# Blip_V1_5.net
KiCad netlist of a schematic drawn in EAGLE
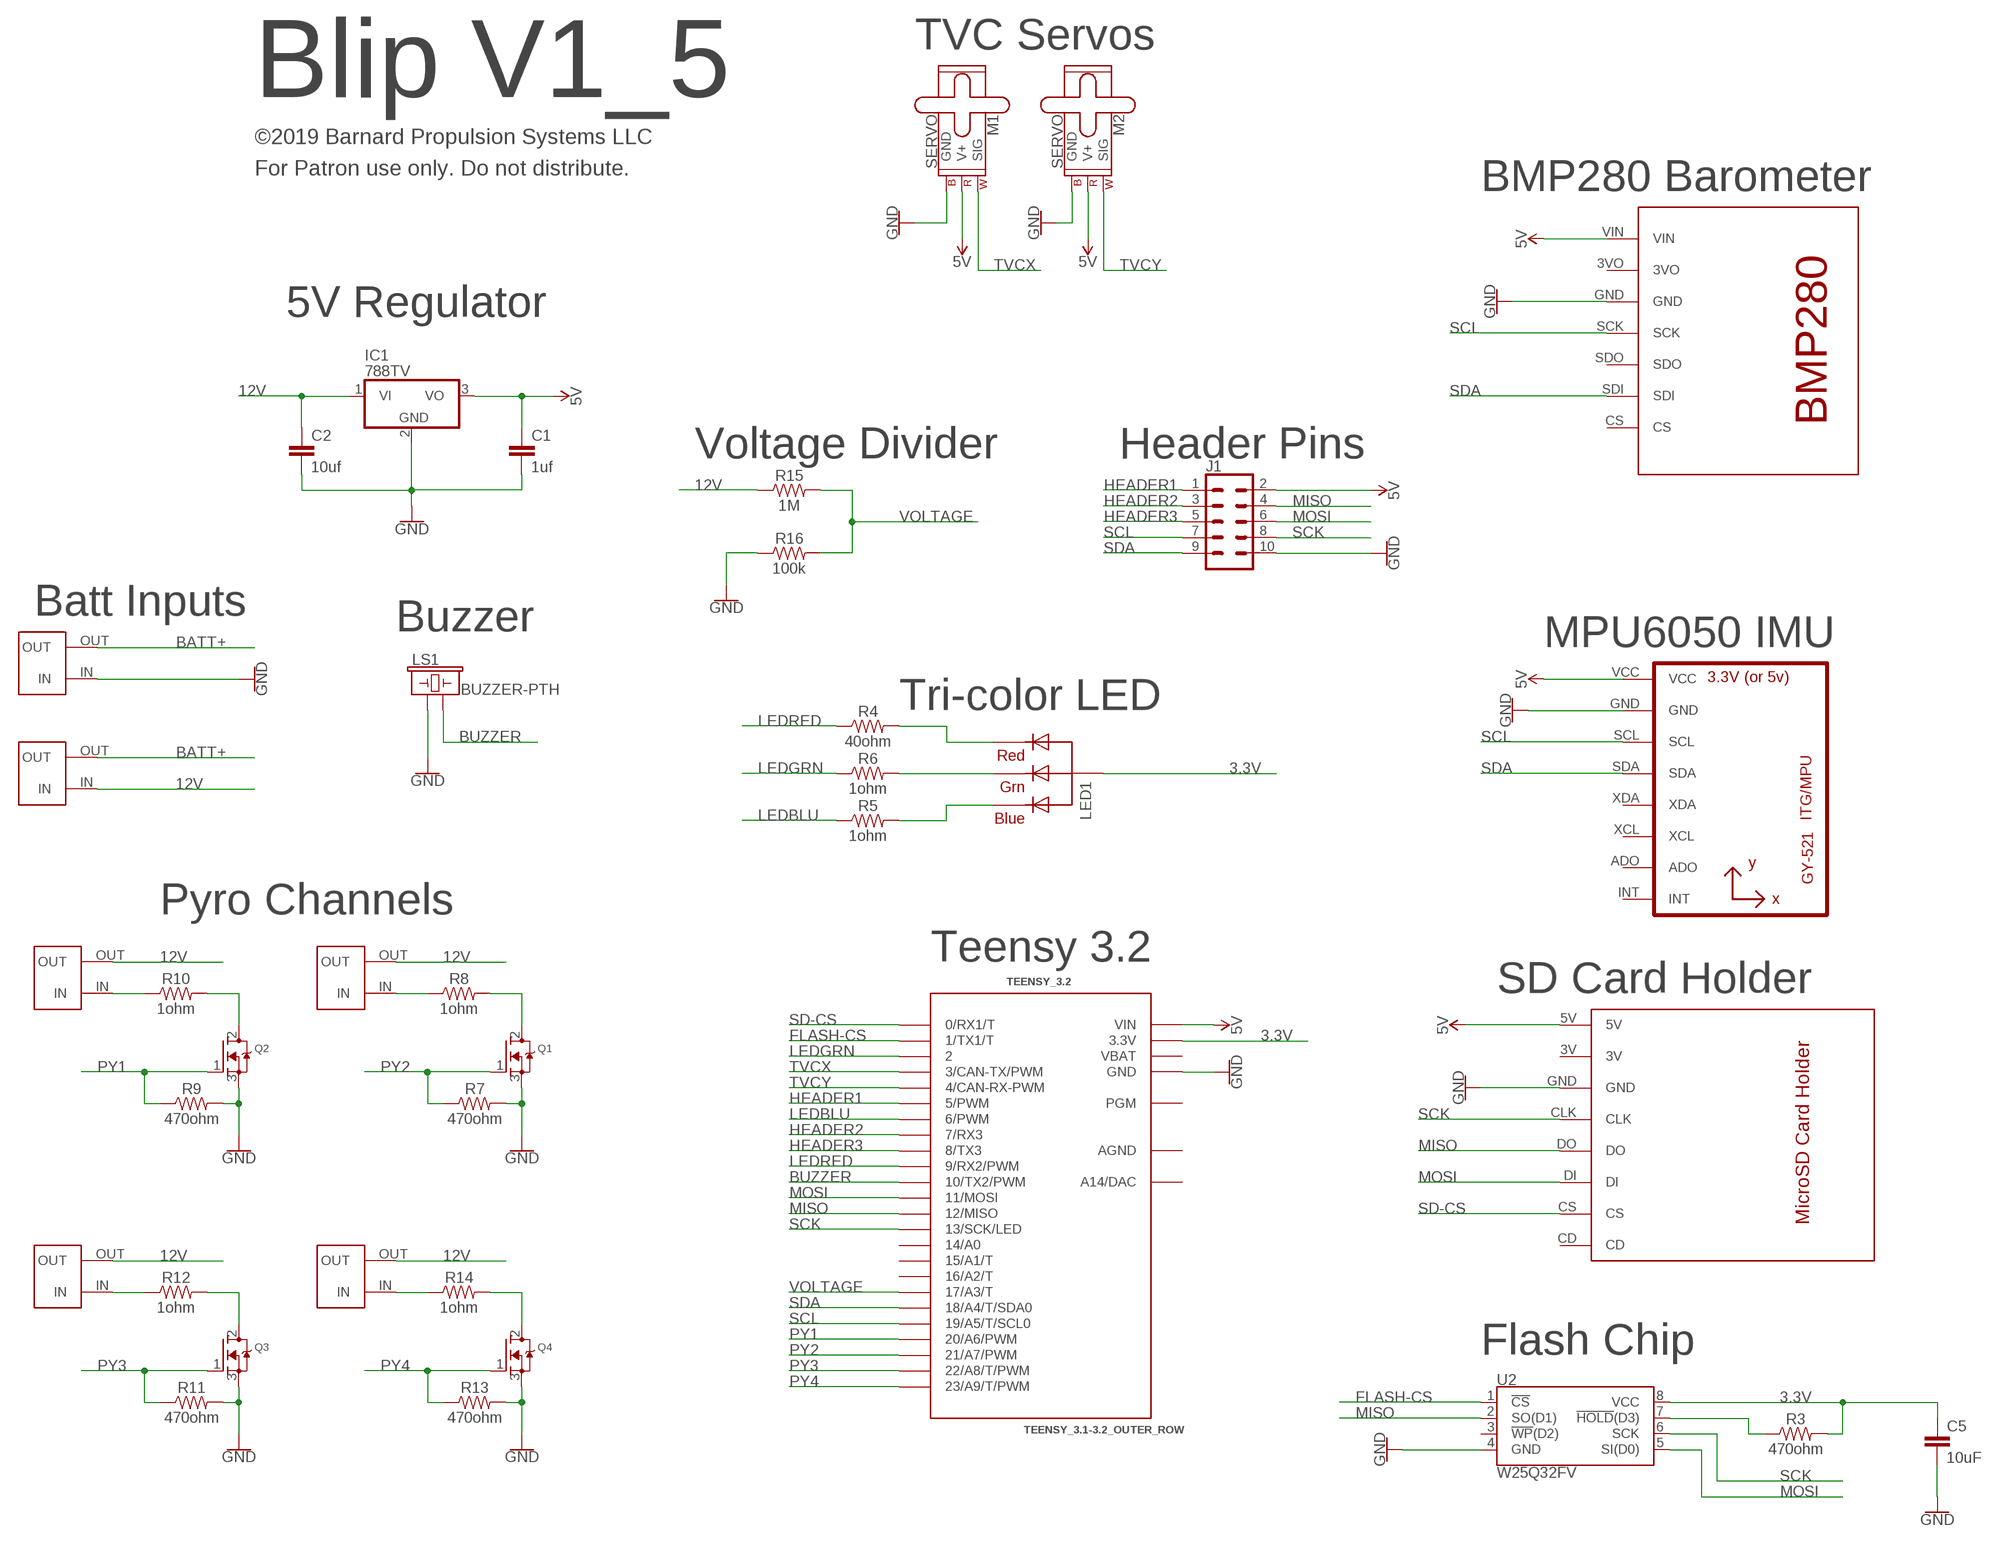
[diagram p0: schematic, sheet 1]

(export (version "E")
  (design (tool "Eeschema 10.0.6"))
  (components
    (comp (ref "C1")
      (value "1uf")
      (footprint "eagle-import:CAP-PTH-2.54")
      (libsource (lib "eagle-import") (part "22PF-PTH-2.54MM-200V-5%"))
    )
    (comp (ref "C2")
      (value "10uf")
      (footprint "eagle-import:CAP-PTH-2.54")
      (libsource (lib "eagle-import") (part "22PF-PTH-2.54MM-200V-5%"))
    )
    (comp (ref "C5")
      (value "10uF")
      (footprint "eagle-import:CAP-PTH-2.54")
      (libsource (lib "eagle-import") (part "22PF-PTH-2.54MM-200V-5%"))
    )
    (comp (ref "IC1")
      (value "788TV")
      (footprint "eagle-import:TO220V")
      (libsource (lib "eagle-import") (part "78TV8"))
    )
    (comp (ref "J1")
      (value "CONN_05X2NO_SILK")
      (footprint "eagle-import:2X5_NOSILK")
      (libsource (lib "eagle-import") (part "CONN_05X2NO_SILK"))
    )
    (comp (ref "LED1")
      (value "RGBLED_CA-5MM")
      (footprint "eagle-import:LED5MMRGB")
      (libsource (lib "eagle-import") (part "RGBLED_CA-5MM"))
    )
    (comp (ref "LS1")
      (value "BUZZER-PTH")
      (footprint "eagle-import:BUZZER-12MM")
      (libsource (lib "eagle-import") (part "BUZZER-PTH"))
    )
    (comp (ref "M1")
      (value "SERVO")
      (footprint "eagle-import:1X03")
      (libsource (lib "eagle-import") (part "SERVO"))
    )
    (comp (ref "M2")
      (value "SERVO")
      (footprint "eagle-import:1X03")
      (libsource (lib "eagle-import") (part "SERVO"))
    )
    (comp (ref "Q1")
      (value "MOSFET-NGDS_TO220V")
      (footprint "eagle-import:TO220V")
      (libsource (lib "eagle-import") (part "MOSFET-NGDS_TO220V"))
    )
    (comp (ref "Q2")
      (value "MOSFET-NGDS_TO220V")
      (footprint "eagle-import:TO220V")
      (libsource (lib "eagle-import") (part "MOSFET-NGDS_TO220V"))
    )
    (comp (ref "Q3")
      (value "MOSFET-NGDS_TO220V")
      (footprint "eagle-import:TO220V")
      (libsource (lib "eagle-import") (part "MOSFET-NGDS_TO220V"))
    )
    (comp (ref "Q4")
      (value "MOSFET-NGDS_TO220V")
      (footprint "eagle-import:TO220V")
      (libsource (lib "eagle-import") (part "MOSFET-NGDS_TO220V"))
    )
    (comp (ref "R3")
      (value "470ohm")
      (footprint "eagle-import:AXIAL-0.3")
      (libsource (lib "eagle-import") (part "10MOHM-HORIZ-1/4W-5%"))
    )
    (comp (ref "R4")
      (value "40ohm")
      (footprint "eagle-import:AXIAL-0.3")
      (libsource (lib "eagle-import") (part "10MOHM-HORIZ-1/4W-5%"))
    )
    (comp (ref "R5")
      (value "1ohm")
      (footprint "eagle-import:AXIAL-0.3")
      (libsource (lib "eagle-import") (part "10MOHM-HORIZ-1/4W-5%"))
    )
    (comp (ref "R6")
      (value "1ohm")
      (footprint "eagle-import:AXIAL-0.3")
      (libsource (lib "eagle-import") (part "10MOHM-HORIZ-1/4W-5%"))
    )
    (comp (ref "R7")
      (value "470ohm")
      (footprint "eagle-import:AXIAL-0.3")
      (libsource (lib "eagle-import") (part "10MOHM-HORIZ-1/4W-5%"))
    )
    (comp (ref "R8")
      (value "1ohm")
      (footprint "eagle-import:AXIAL-0.3")
      (libsource (lib "eagle-import") (part "10MOHM-HORIZ-1/4W-5%"))
    )
    (comp (ref "R9")
      (value "470ohm")
      (footprint "eagle-import:AXIAL-0.3")
      (libsource (lib "eagle-import") (part "10MOHM-HORIZ-1/4W-5%"))
    )
    (comp (ref "R10")
      (value "1ohm")
      (footprint "eagle-import:AXIAL-0.3")
      (libsource (lib "eagle-import") (part "10MOHM-HORIZ-1/4W-5%"))
    )
    (comp (ref "R11")
      (value "470ohm")
      (footprint "eagle-import:AXIAL-0.3")
      (libsource (lib "eagle-import") (part "10MOHM-HORIZ-1/4W-5%"))
    )
    (comp (ref "R12")
      (value "1ohm")
      (footprint "eagle-import:AXIAL-0.3")
      (libsource (lib "eagle-import") (part "10MOHM-HORIZ-1/4W-5%"))
    )
    (comp (ref "R13")
      (value "470ohm")
      (footprint "eagle-import:AXIAL-0.3")
      (libsource (lib "eagle-import") (part "10MOHM-HORIZ-1/4W-5%"))
    )
    (comp (ref "R14")
      (value "1ohm")
      (footprint "eagle-import:AXIAL-0.3")
      (libsource (lib "eagle-import") (part "10MOHM-HORIZ-1/4W-5%"))
    )
    (comp (ref "R15")
      (value "1M")
      (footprint "eagle-import:AXIAL-0.3")
      (libsource (lib "eagle-import") (part "10MOHM-HORIZ-1/4W-5%"))
    )
    (comp (ref "R16")
      (value "100k")
      (footprint "eagle-import:AXIAL-0.3")
      (libsource (lib "eagle-import") (part "10MOHM-HORIZ-1/4W-5%"))
    )
    (comp (ref "TEENSY_3.2")
      (value "TEENSY_3.1-3.2_OUTER_ROW")
      (footprint "eagle-import:TEENSY_3.0-3.2&LC_OUTER_ROW")
      (libsource (lib "eagle-import") (part "TEENSY_3.1-3.2_OUTER_ROW"))
    )
    (comp (ref "U$2")
      (value "BMP280")
      (footprint "eagle-import:BMP280")
      (libsource (lib "eagle-import") (part "BMP280"))
    )
    (comp (ref "U$3")
      (value "MICROSDCARDHOLDER")
      (footprint "eagle-import:SDCARDHOLDER")
      (libsource (lib "eagle-import") (part "MICROSDCARDHOLDER"))
    )
    (comp (ref "U$4")
      (value "BLACKTERMBLOCK")
      (footprint "eagle-import:BLACKTERMBLOCK")
      (libsource (lib "eagle-import") (part "BLACKTERMBLOCK"))
    )
    (comp (ref "U$5")
      (value "BLACKTERMBLOCK")
      (footprint "eagle-import:BLACKTERMBLOCK")
      (libsource (lib "eagle-import") (part "BLACKTERMBLOCK"))
    )
    (comp (ref "U$6")
      (value "BLACKTERMBLOCK")
      (footprint "eagle-import:BLACKTERMBLOCK")
      (libsource (lib "eagle-import") (part "BLACKTERMBLOCK"))
    )
    (comp (ref "U$7")
      (value "BLACKTERMBLOCK")
      (footprint "eagle-import:BLACKTERMBLOCK")
      (libsource (lib "eagle-import") (part "BLACKTERMBLOCK"))
    )
    (comp (ref "U$8")
      (value "BLACKTERMBLOCK")
      (footprint "eagle-import:BLACKTERMBLOCK")
      (libsource (lib "eagle-import") (part "BLACKTERMBLOCK"))
    )
    (comp (ref "U$9")
      (value "BLACKTERMBLOCK")
      (footprint "eagle-import:BLACKTERMBLOCK")
      (libsource (lib "eagle-import") (part "BLACKTERMBLOCK"))
    )
    (comp (ref "U1")
      (value "GY-521MPU6050")
      (footprint "eagle-import:GY-521")
      (libsource (lib "eagle-import") (part "GY-521MPU6050"))
    )
    (comp (ref "U2")
      (value "W25Q32FV")
      (footprint "eagle-import:SOIC-8")
      (libsource (lib "eagle-import") (part "W25Q32FVSS"))
    )
  )
  (nets
    (net (code "1") (name "/3.3V") (class "Default")
      (node (ref "C5") (pin "1") (pinfunction "1_1") (pintype "passive"))
      (node (ref "LED1") (pin "2") (pinfunction "VCC_2") (pintype "bidirectional"))
      (node (ref "R3") (pin "P$2") (pinfunction "2_P$2") (pintype "passive"))
      (node (ref "TEENSY_3.2") (pin "3.3V") (pinfunction "3.3V_3.3V") (pintype "power_in"))
      (node (ref "TEENSY_3.2") (pin "3.3V1") (pinfunction "3.3V_3.3V1") (pintype "power_in"))
      (node (ref "U2") (pin "8") (pinfunction "VCC_8") (pintype "bidirectional"))
    )
    (net (code "2") (name "/12V") (class "Default")
      (node (ref "C2") (pin "1") (pinfunction "1_1") (pintype "passive"))
      (node (ref "IC1") (pin "1") (pinfunction "VI_1") (pintype "input"))
      (node (ref "R15") (pin "P$1") (pinfunction "1_P$1") (pintype "passive"))
      (node (ref "U$4") (pin "OUT") (pinfunction "OUT_OUT") (pintype "bidirectional"))
      (node (ref "U$5") (pin "OUT") (pinfunction "OUT_OUT") (pintype "bidirectional"))
      (node (ref "U$6") (pin "OUT") (pinfunction "OUT_OUT") (pintype "bidirectional"))
      (node (ref "U$7") (pin "OUT") (pinfunction "OUT_OUT") (pintype "bidirectional"))
      (node (ref "U$9") (pin "IN") (pinfunction "IN_IN") (pintype "bidirectional"))
    )
    (net (code "3") (name "/AGND") (class "Default")
      (node (ref "TEENSY_3.2") (pin "AGND") (pinfunction "AGND_AGND") (pintype "power_in"))
    )
    (net (code "4") (name "/BATT+") (class "Default")
      (node (ref "U$8") (pin "OUT") (pinfunction "OUT_OUT") (pintype "bidirectional"))
      (node (ref "U$9") (pin "OUT") (pinfunction "OUT_OUT") (pintype "bidirectional"))
    )
    (net (code "5") (name "/BUZZER") (class "Default")
      (node (ref "LS1") (pin "-") (pinfunction "2_-") (pintype "passive"))
      (node (ref "TEENSY_3.2") (pin "10") (pinfunction "10/TX2/PWM_10") (pintype "bidirectional"))
    )
    (net (code "6") (name "/FLASH-CS") (class "Default")
      (node (ref "TEENSY_3.2") (pin "1") (pinfunction "1/TX1/T_1") (pintype "bidirectional"))
      (node (ref "U2") (pin "1") (pinfunction "~{CS}_1") (pintype "bidirectional"))
    )
    (net (code "7") (name "/HEADER1") (class "Default")
      (node (ref "J1") (pin "1") (pinfunction "1_1") (pintype "passive"))
      (node (ref "TEENSY_3.2") (pin "5") (pinfunction "5/PWM_5") (pintype "bidirectional"))
    )
    (net (code "8") (name "/HEADER2") (class "Default")
      (node (ref "J1") (pin "3") (pinfunction "3_3") (pintype "passive"))
      (node (ref "TEENSY_3.2") (pin "7") (pinfunction "7/RX3_7") (pintype "bidirectional"))
    )
    (net (code "9") (name "/HEADER3") (class "Default")
      (node (ref "J1") (pin "5") (pinfunction "5_5") (pintype "passive"))
      (node (ref "TEENSY_3.2") (pin "8") (pinfunction "8/TX3_8") (pintype "bidirectional"))
    )
    (net (code "10") (name "/LEDBLU") (class "Default")
      (node (ref "R5") (pin "P$1") (pinfunction "1_P$1") (pintype "passive"))
      (node (ref "TEENSY_3.2") (pin "6") (pinfunction "6/PWM_6") (pintype "bidirectional"))
    )
    (net (code "11") (name "/LEDGRN") (class "Default")
      (node (ref "R6") (pin "P$1") (pinfunction "1_P$1") (pintype "passive"))
      (node (ref "TEENSY_3.2") (pin "2") (pinfunction "2_2") (pintype "bidirectional"))
    )
    (net (code "12") (name "/LEDRED") (class "Default")
      (node (ref "R4") (pin "P$1") (pinfunction "1_P$1") (pintype "passive"))
      (node (ref "TEENSY_3.2") (pin "9") (pinfunction "9/RX2/PWM_9") (pintype "bidirectional"))
    )
    (net (code "13") (name "/MISO") (class "Default")
      (node (ref "J1") (pin "4") (pinfunction "4_4") (pintype "passive"))
      (node (ref "TEENSY_3.2") (pin "12") (pinfunction "12/MISO_12") (pintype "bidirectional"))
      (node (ref "U$3") (pin "DO") (pinfunction "DO_DO") (pintype "bidirectional"))
      (node (ref "U2") (pin "2") (pinfunction "SO(D1)_2") (pintype "bidirectional"))
    )
    (net (code "14") (name "/MOSI") (class "Default")
      (node (ref "J1") (pin "6") (pinfunction "6_6") (pintype "passive"))
      (node (ref "TEENSY_3.2") (pin "11") (pinfunction "11/MOSI_11") (pintype "bidirectional"))
      (node (ref "U$3") (pin "DI") (pinfunction "DI_DI") (pintype "bidirectional"))
      (node (ref "U2") (pin "5") (pinfunction "SI(D0)_5") (pintype "bidirectional"))
    )
    (net (code "15") (name "/PY1") (class "Default")
      (node (ref "Q2") (pin "1") (pinfunction "G_1") (pintype "bidirectional"))
      (node (ref "R9") (pin "P$1") (pinfunction "1_P$1") (pintype "passive"))
      (node (ref "TEENSY_3.2") (pin "20/A6") (pinfunction "20/A6/PWM_20/A6") (pintype "bidirectional"))
    )
    (net (code "16") (name "/PY2") (class "Default")
      (node (ref "Q1") (pin "1") (pinfunction "G_1") (pintype "bidirectional"))
      (node (ref "R7") (pin "P$1") (pinfunction "1_P$1") (pintype "passive"))
      (node (ref "TEENSY_3.2") (pin "21/A7") (pinfunction "21/A7/PWM_21/A7") (pintype "bidirectional"))
    )
    (net (code "17") (name "/PY3") (class "Default")
      (node (ref "Q3") (pin "1") (pinfunction "G_1") (pintype "bidirectional"))
      (node (ref "R11") (pin "P$1") (pinfunction "1_P$1") (pintype "passive"))
      (node (ref "TEENSY_3.2") (pin "22/A8") (pinfunction "22/A8/T/PWM_22/A8") (pintype "bidirectional"))
    )
    (net (code "18") (name "/PY4") (class "Default")
      (node (ref "Q4") (pin "1") (pinfunction "G_1") (pintype "bidirectional"))
      (node (ref "R13") (pin "P$1") (pinfunction "1_P$1") (pintype "passive"))
      (node (ref "TEENSY_3.2") (pin "23/A9") (pinfunction "23/A9/T/PWM_23/A9") (pintype "bidirectional"))
    )
    (net (code "19") (name "/SCK") (class "Default")
      (node (ref "J1") (pin "8") (pinfunction "8_8") (pintype "passive"))
      (node (ref "TEENSY_3.2") (pin "13") (pinfunction "13/SCK/LED_13") (pintype "bidirectional"))
      (node (ref "U$3") (pin "CLK") (pinfunction "CLK_CLK") (pintype "bidirectional"))
      (node (ref "U2") (pin "6") (pinfunction "SCK_6") (pintype "bidirectional"))
    )
    (net (code "20") (name "/SCL") (class "Default")
      (node (ref "J1") (pin "7") (pinfunction "7_7") (pintype "passive"))
      (node (ref "TEENSY_3.2") (pin "19/A5") (pinfunction "19/A5/T/SCL0_19/A5") (pintype "bidirectional"))
      (node (ref "U$2") (pin "SCK") (pinfunction "SCK_SCK") (pintype "bidirectional"))
      (node (ref "U1") (pin "SCL") (pinfunction "SCL_SCL") (pintype "bidirectional"))
    )
    (net (code "21") (name "/SD-CS") (class "Default")
      (node (ref "TEENSY_3.2") (pin "0") (pinfunction "0/RX1/T_0") (pintype "bidirectional"))
      (node (ref "U$3") (pin "CS") (pinfunction "CS_CS") (pintype "bidirectional"))
    )
    (net (code "22") (name "/SDA") (class "Default")
      (node (ref "J1") (pin "9") (pinfunction "9_9") (pintype "passive"))
      (node (ref "TEENSY_3.2") (pin "18/A4") (pinfunction "18/A4/T/SDA0_18/A4") (pintype "bidirectional"))
      (node (ref "U$2") (pin "SDI") (pinfunction "SDI_SDI") (pintype "bidirectional"))
      (node (ref "U1") (pin "SDA") (pinfunction "SDA_SDA") (pintype "bidirectional"))
    )
    (net (code "23") (name "/TVCX") (class "Default")
      (node (ref "M1") (pin "1") (pinfunction "SIG_1") (pintype "bidirectional"))
      (node (ref "TEENSY_3.2") (pin "3") (pinfunction "3/CAN-TX/PWM_3") (pintype "bidirectional"))
    )
    (net (code "24") (name "/TVCY") (class "Default")
      (node (ref "M2") (pin "1") (pinfunction "SIG_1") (pintype "bidirectional"))
      (node (ref "TEENSY_3.2") (pin "4") (pinfunction "4/CAN-RX-PWM_4") (pintype "bidirectional"))
    )
    (net (code "25") (name "/VBAT") (class "Default")
      (node (ref "TEENSY_3.2") (pin "VBAT") (pinfunction "VBAT_VBAT") (pintype "power_in"))
    )
    (net (code "26") (name "/VOLTAGE") (class "Default")
      (node (ref "R15") (pin "P$2") (pinfunction "2_P$2") (pintype "passive"))
      (node (ref "R16") (pin "P$2") (pinfunction "2_P$2") (pintype "passive"))
      (node (ref "TEENSY_3.2") (pin "17/A3") (pinfunction "17/A3/T_17/A3") (pintype "bidirectional"))
    )
    (net (code "27") (name "5V") (class "Default")
      (node (ref "C1") (pin "1") (pinfunction "1_1") (pintype "passive"))
      (node (ref "IC1") (pin "3") (pinfunction "VO_3") (pintype "passive"))
      (node (ref "J1") (pin "2") (pinfunction "2_2") (pintype "passive"))
      (node (ref "M1") (pin "2") (pinfunction "V+_2") (pintype "bidirectional"))
      (node (ref "M2") (pin "2") (pinfunction "V+_2") (pintype "bidirectional"))
      (node (ref "TEENSY_3.2") (pin "VIN") (pinfunction "VIN_VIN") (pintype "power_in"))
      (node (ref "U$2") (pin "VIN") (pinfunction "VIN_VIN") (pintype "bidirectional"))
      (node (ref "U$3") (pin "5V") (pinfunction "5V_5V") (pintype "bidirectional"))
      (node (ref "U1") (pin "VCC") (pinfunction "VCC_VCC") (pintype "bidirectional"))
    )
    (net (code "28") (name "GND") (class "Default")
      (node (ref "C1") (pin "2") (pinfunction "2_2") (pintype "passive"))
      (node (ref "C2") (pin "2") (pinfunction "2_2") (pintype "passive"))
      (node (ref "C5") (pin "2") (pinfunction "2_2") (pintype "passive"))
      (node (ref "IC1") (pin "2") (pinfunction "GND_2") (pintype "passive"))
      (node (ref "J1") (pin "10") (pinfunction "10_10") (pintype "passive"))
      (node (ref "LS1") (pin "+") (pinfunction "1_+") (pintype "passive"))
      (node (ref "M1") (pin "3") (pinfunction "GND_3") (pintype "bidirectional"))
      (node (ref "M2") (pin "3") (pinfunction "GND_3") (pintype "bidirectional"))
      (node (ref "Q1") (pin "3") (pinfunction "S_3") (pintype "bidirectional"))
      (node (ref "Q2") (pin "3") (pinfunction "S_3") (pintype "bidirectional"))
      (node (ref "Q3") (pin "3") (pinfunction "S_3") (pintype "bidirectional"))
      (node (ref "Q4") (pin "3") (pinfunction "S_3") (pintype "bidirectional"))
      (node (ref "R11") (pin "P$2") (pinfunction "2_P$2") (pintype "passive"))
      (node (ref "R13") (pin "P$2") (pinfunction "2_P$2") (pintype "passive"))
      (node (ref "R16") (pin "P$1") (pinfunction "1_P$1") (pintype "passive"))
      (node (ref "R7") (pin "P$2") (pinfunction "2_P$2") (pintype "passive"))
      (node (ref "R9") (pin "P$2") (pinfunction "2_P$2") (pintype "passive"))
      (node (ref "TEENSY_3.2") (pin "GND") (pinfunction "GND_GND") (pintype "power_in"))
      (node (ref "TEENSY_3.2") (pin "GND1") (pinfunction "GND_GND1") (pintype "power_in"))
      (node (ref "U$2") (pin "GND") (pinfunction "GND_GND") (pintype "bidirectional"))
      (node (ref "U$3") (pin "GND") (pinfunction "GND_GND") (pintype "bidirectional"))
      (node (ref "U$8") (pin "IN") (pinfunction "IN_IN") (pintype "bidirectional"))
      (node (ref "U1") (pin "GND") (pinfunction "GND_GND") (pintype "bidirectional"))
      (node (ref "U2") (pin "4") (pinfunction "GND_4") (pintype "bidirectional"))
    )
    (net (code "29") (name "Net-(LED1-BLUE)") (class "Default")
      (node (ref "LED1") (pin "4") (pinfunction "BLUE_4") (pintype "bidirectional"))
      (node (ref "R5") (pin "P$2") (pinfunction "2_P$2") (pintype "passive"))
    )
    (net (code "30") (name "Net-(LED1-GREEN)") (class "Default")
      (node (ref "LED1") (pin "3") (pinfunction "GREEN_3") (pintype "bidirectional"))
      (node (ref "R6") (pin "P$2") (pinfunction "2_P$2") (pintype "passive"))
    )
    (net (code "31") (name "Net-(LED1-RED)") (class "Default")
      (node (ref "LED1") (pin "1") (pinfunction "RED_1") (pintype "bidirectional"))
      (node (ref "R4") (pin "P$2") (pinfunction "2_P$2") (pintype "passive"))
    )
    (net (code "32") (name "Net-(Q1-D)") (class "Default")
      (node (ref "Q1") (pin "2") (pinfunction "D_2") (pintype "bidirectional"))
      (node (ref "R8") (pin "P$2") (pinfunction "2_P$2") (pintype "passive"))
    )
    (net (code "33") (name "Net-(Q2-D)") (class "Default")
      (node (ref "Q2") (pin "2") (pinfunction "D_2") (pintype "bidirectional"))
      (node (ref "R10") (pin "P$2") (pinfunction "2_P$2") (pintype "passive"))
    )
    (net (code "34") (name "Net-(Q3-D)") (class "Default")
      (node (ref "Q3") (pin "2") (pinfunction "D_2") (pintype "bidirectional"))
      (node (ref "R12") (pin "P$2") (pinfunction "2_P$2") (pintype "passive"))
    )
    (net (code "35") (name "Net-(Q4-D)") (class "Default")
      (node (ref "Q4") (pin "2") (pinfunction "D_2") (pintype "bidirectional"))
      (node (ref "R14") (pin "P$2") (pinfunction "2_P$2") (pintype "passive"))
    )
    (net (code "36") (name "Net-(R3-1)") (class "Default")
      (node (ref "R3") (pin "P$1") (pinfunction "1_P$1") (pintype "passive"))
      (node (ref "U2") (pin "7") (pinfunction "~{HOLD}(D3)_7") (pintype "bidirectional"))
    )
    (net (code "37") (name "Net-(R8-1)") (class "Default")
      (node (ref "R8") (pin "P$1") (pinfunction "1_P$1") (pintype "passive"))
      (node (ref "U$4") (pin "IN") (pinfunction "IN_IN") (pintype "bidirectional"))
    )
    (net (code "38") (name "Net-(R10-1)") (class "Default")
      (node (ref "R10") (pin "P$1") (pinfunction "1_P$1") (pintype "passive"))
      (node (ref "U$5") (pin "IN") (pinfunction "IN_IN") (pintype "bidirectional"))
    )
    (net (code "39") (name "Net-(R12-1)") (class "Default")
      (node (ref "R12") (pin "P$1") (pinfunction "1_P$1") (pintype "passive"))
      (node (ref "U$6") (pin "IN") (pinfunction "IN_IN") (pintype "bidirectional"))
    )
    (net (code "40") (name "Net-(R14-1)") (class "Default")
      (node (ref "R14") (pin "P$1") (pinfunction "1_P$1") (pintype "passive"))
      (node (ref "U$7") (pin "IN") (pinfunction "IN_IN") (pintype "bidirectional"))
    )
    (net (code "41") (name "unconnected-(TEENSY_3.2-15{slash}A1{slash}T-Pad15{slash}A1)") (class "Default")
      (node (ref "TEENSY_3.2") (pin "15/A1") (pinfunction "15/A1/T_15/A1") (pintype "bidirectional"))
    )
    (net (code "42") (name "unconnected-(TEENSY_3.2-16{slash}A2{slash}T-Pad16{slash}A2)") (class "Default")
      (node (ref "TEENSY_3.2") (pin "16/A2") (pinfunction "16/A2/T_16/A2") (pintype "bidirectional"))
    )
    (net (code "43") (name "unconnected-(TEENSY_3.2-A14{slash}DAC-PadRESET{slash}DAC)") (class "Default")
      (node (ref "TEENSY_3.2") (pin "RESET/DAC") (pinfunction "A14/DAC_RESET/DAC") (pintype "bidirectional"))
    )
    (net (code "44") (name "unconnected-(TEENSY_3.2-Pad14{slash}A0)") (class "Default")
      (node (ref "TEENSY_3.2") (pin "14/A0") (pinfunction "14/A0_14/A0") (pintype "bidirectional"))
    )
    (net (code "45") (name "unconnected-(TEENSY_3.2-PadPGM)") (class "Default")
      (node (ref "TEENSY_3.2") (pin "PGM") (pinfunction "PGM_PGM") (pintype "bidirectional"))
    )
    (net (code "46") (name "unconnected-(U$2-Pad3VO)") (class "Default")
      (node (ref "U$2") (pin "3VO") (pinfunction "3VO_3VO") (pintype "bidirectional"))
    )
    (net (code "47") (name "unconnected-(U$2-PadCS)") (class "Default")
      (node (ref "U$2") (pin "CS") (pinfunction "CS_CS") (pintype "bidirectional"))
    )
    (net (code "48") (name "unconnected-(U$2-PadSDO)") (class "Default")
      (node (ref "U$2") (pin "SDO") (pinfunction "SDO_SDO") (pintype "bidirectional"))
    )
    (net (code "49") (name "unconnected-(U$3-Pad3V)") (class "Default")
      (node (ref "U$3") (pin "3V") (pinfunction "3V_3V") (pintype "bidirectional"))
    )
    (net (code "50") (name "unconnected-(U$3-PadCD)") (class "Default")
      (node (ref "U$3") (pin "CD") (pinfunction "CD_CD") (pintype "bidirectional"))
    )
    (net (code "51") (name "unconnected-(U1-PadADO)") (class "Default")
      (node (ref "U1") (pin "ADO") (pinfunction "ADO_ADO") (pintype "bidirectional"))
    )
    (net (code "52") (name "unconnected-(U1-PadINT)") (class "Default")
      (node (ref "U1") (pin "INT") (pinfunction "INT_INT") (pintype "bidirectional"))
    )
    (net (code "53") (name "unconnected-(U1-PadXCL)") (class "Default")
      (node (ref "U1") (pin "XCL") (pinfunction "XCL_XCL") (pintype "bidirectional"))
    )
    (net (code "54") (name "unconnected-(U1-PadXDA)") (class "Default")
      (node (ref "U1") (pin "XDA") (pinfunction "XDA_XDA") (pintype "bidirectional"))
    )
    (net (code "55") (name "unconnected-(U2-~{WP}(D2)-Pad3)") (class "Default")
      (node (ref "U2") (pin "3") (pinfunction "~{WP}(D2)_3") (pintype "bidirectional"))
    )
  )
)
